# Lab_6_CTD.net
KiCad netlist of a schematic drawn in EAGLE
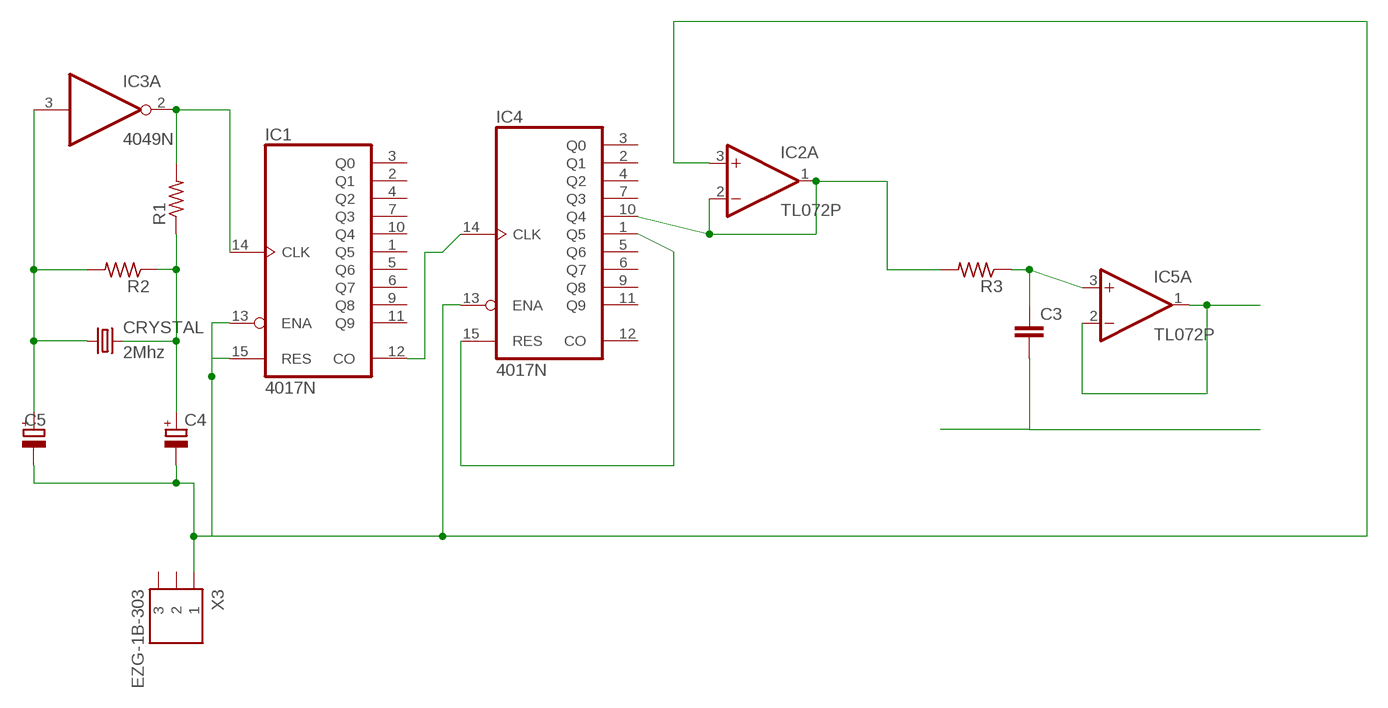
[diagram p0: schematic, sheet 1]

(export (version "E")
  (design (tool "Eeschema 10.0.6"))
  (components
    (comp (ref "C3")
      (value "C-EU050-025X075")
      (footprint "eagle-import:C050-025X075")
      (libsource (lib "eagle-import") (part "C-EU050-025X075"))
    )
    (comp (ref "C4")
      (value "CPOL-EUB45181A")
      (footprint "eagle-import:B45181A")
      (libsource (lib "eagle-import") (part "CPOL-EUB45181A"))
    )
    (comp (ref "C5")
      (value "CPOL-EUB45181A")
      (footprint "eagle-import:B45181A")
      (libsource (lib "eagle-import") (part "CPOL-EUB45181A"))
    )
    (comp (ref "CRYSTAL")
      (value "2Mhz")
      (footprint "eagle-import:HC49U-V")
      (libsource (lib "eagle-import") (part "CRYSTALHC49U-V"))
    )
    (comp (ref "IC1")
      (value "4017N")
      (footprint "eagle-import:DIL16")
      (libsource (lib "eagle-import") (part "4017N"))
    )
    (comp (ref "IC2")
      (value "TL072P")
      (footprint "eagle-import:DIL08")
      (libsource (lib "eagle-import") (part "TL072P"))
    )
    (comp (ref "IC3")
      (value "4049N")
      (footprint "eagle-import:DIL16")
      (libsource (lib "eagle-import") (part "4049N"))
    )
    (comp (ref "IC4")
      (value "4017N")
      (footprint "eagle-import:DIL16")
      (libsource (lib "eagle-import") (part "4017N"))
    )
    (comp (ref "IC5")
      (value "TL072P")
      (footprint "eagle-import:DIL08")
      (libsource (lib "eagle-import") (part "TL072P"))
    )
    (comp (ref "R1")
      (value "R-US_0411/15")
      (footprint "eagle-import:0411_15")
      (libsource (lib "eagle-import") (part "R-US_0411/15"))
    )
    (comp (ref "R2")
      (value "R-US_0411/15")
      (footprint "eagle-import:0411_15")
      (libsource (lib "eagle-import") (part "R-US_0411/15"))
    )
    (comp (ref "R3")
      (value "R-US_0411/15")
      (footprint "eagle-import:0411_15")
      (libsource (lib "eagle-import") (part "R-US_0411/15"))
    )
    (comp (ref "X3")
      (value "EZG-1B-303")
      (footprint "eagle-import:EZG-1B-1K-303")
      (libsource (lib "eagle-import") (part "EZG-?-3031B"))
    )
  )
  (nets
    (net (code "1") (name "Net-(C4-Pad+)") (class "Default")
      (node (ref "C4") (pin "+") (pinfunction "+_+") (pintype "passive"))
      (node (ref "CRYSTAL") (pin "2") (pinfunction "2_2") (pintype "passive"))
      (node (ref "R1") (pin "1") (pinfunction "1_1") (pintype "passive"))
      (node (ref "R2") (pin "1") (pinfunction "1_1") (pintype "passive"))
    )
    (net (code "2") (name "Net-(IC1A-CLK)") (class "Default")
      (node (ref "IC1") (pin "14") (pinfunction "CLK_14") (pintype "input"))
      (node (ref "IC3") (pin "2") (pinfunction "O_2") (pintype "output"))
      (node (ref "R1") (pin "2") (pinfunction "2_2") (pintype "passive"))
    )
    (net (code "3") (name "Net-(IC1A-CO)") (class "Default")
      (node (ref "IC1") (pin "12") (pinfunction "CO_12") (pintype "output"))
      (node (ref "IC4") (pin "14") (pinfunction "CLK_14") (pintype "input"))
    )
    (net (code "4") (name "Net-(IC1A-ENA)") (class "Default")
      (node (ref "C4") (pin "-") (pinfunction "-_-") (pintype "passive"))
      (node (ref "C5") (pin "-") (pinfunction "-_-") (pintype "passive"))
      (node (ref "IC1") (pin "13") (pinfunction "ENA_13") (pintype "input"))
      (node (ref "IC1") (pin "15") (pinfunction "RES_15") (pintype "input"))
      (node (ref "IC2") (pin "3") (pinfunction "+IN_3") (pintype "input"))
      (node (ref "IC4") (pin "13") (pinfunction "ENA_13") (pintype "input"))
      (node (ref "X3") (pin "1") (pinfunction "1_1") (pintype "passive"))
    )
    (net (code "5") (name "Net-(IC2A--IN)") (class "Default")
      (node (ref "IC2") (pin "1") (pinfunction "OUT_1") (pintype "output"))
      (node (ref "IC2") (pin "2") (pinfunction "-IN_2") (pintype "input"))
      (node (ref "IC4") (pin "10") (pinfunction "Q4_10") (pintype "output"))
      (node (ref "R3") (pin "2") (pinfunction "2_2") (pintype "passive"))
    )
    (net (code "6") (name "Net-(IC3A-I)") (class "Default")
      (node (ref "C5") (pin "+") (pinfunction "+_+") (pintype "passive"))
      (node (ref "CRYSTAL") (pin "1") (pinfunction "1_1") (pintype "passive"))
      (node (ref "IC3") (pin "3") (pinfunction "I_3") (pintype "input"))
      (node (ref "R2") (pin "2") (pinfunction "2_2") (pintype "passive"))
    )
    (net (code "7") (name "Net-(IC4A-Q5)") (class "Default")
      (node (ref "IC4") (pin "1") (pinfunction "Q5_1") (pintype "output"))
      (node (ref "IC4") (pin "15") (pinfunction "RES_15") (pintype "input"))
    )
    (net (code "8") (name "Net-(IC5A-+IN)") (class "Default")
      (node (ref "C3") (pin "1") (pinfunction "1_1") (pintype "passive"))
      (node (ref "IC5") (pin "3") (pinfunction "+IN_3") (pintype "input"))
      (node (ref "R3") (pin "1") (pinfunction "1_1") (pintype "passive"))
    )
    (net (code "9") (name "Net-(IC5A--IN)") (class "Default")
      (node (ref "IC5") (pin "1") (pinfunction "OUT_1") (pintype "output"))
      (node (ref "IC5") (pin "2") (pinfunction "-IN_2") (pintype "input"))
    )
    (net (code "10") (name "unconnected-(C3-Pad2)") (class "Default")
      (node (ref "C3") (pin "2") (pinfunction "2_2") (pintype "passive"))
    )
    (net (code "11") (name "unconnected-(IC1A-Q0-Pad3)") (class "Default")
      (node (ref "IC1") (pin "3") (pinfunction "Q0_3") (pintype "output"))
    )
    (net (code "12") (name "unconnected-(IC1A-Q1-Pad2)") (class "Default")
      (node (ref "IC1") (pin "2") (pinfunction "Q1_2") (pintype "output"))
    )
    (net (code "13") (name "unconnected-(IC1A-Q2-Pad4)") (class "Default")
      (node (ref "IC1") (pin "4") (pinfunction "Q2_4") (pintype "output"))
    )
    (net (code "14") (name "unconnected-(IC1A-Q3-Pad7)") (class "Default")
      (node (ref "IC1") (pin "7") (pinfunction "Q3_7") (pintype "output"))
    )
    (net (code "15") (name "unconnected-(IC1A-Q4-Pad10)") (class "Default")
      (node (ref "IC1") (pin "10") (pinfunction "Q4_10") (pintype "output"))
    )
    (net (code "16") (name "unconnected-(IC1A-Q5-Pad1)") (class "Default")
      (node (ref "IC1") (pin "1") (pinfunction "Q5_1") (pintype "output"))
    )
    (net (code "17") (name "unconnected-(IC1A-Q6-Pad5)") (class "Default")
      (node (ref "IC1") (pin "5") (pinfunction "Q6_5") (pintype "output"))
    )
    (net (code "18") (name "unconnected-(IC1A-Q7-Pad6)") (class "Default")
      (node (ref "IC1") (pin "6") (pinfunction "Q7_6") (pintype "output"))
    )
    (net (code "19") (name "unconnected-(IC1A-Q8-Pad9)") (class "Default")
      (node (ref "IC1") (pin "9") (pinfunction "Q8_9") (pintype "output"))
    )
    (net (code "20") (name "unconnected-(IC1A-Q9-Pad11)") (class "Default")
      (node (ref "IC1") (pin "11") (pinfunction "Q9_11") (pintype "output"))
    )
    (net (code "21") (name "unconnected-(IC4A-CO-Pad12)") (class "Default")
      (node (ref "IC4") (pin "12") (pinfunction "CO_12") (pintype "output"))
    )
    (net (code "22") (name "unconnected-(IC4A-Q0-Pad3)") (class "Default")
      (node (ref "IC4") (pin "3") (pinfunction "Q0_3") (pintype "output"))
    )
    (net (code "23") (name "unconnected-(IC4A-Q1-Pad2)") (class "Default")
      (node (ref "IC4") (pin "2") (pinfunction "Q1_2") (pintype "output"))
    )
    (net (code "24") (name "unconnected-(IC4A-Q2-Pad4)") (class "Default")
      (node (ref "IC4") (pin "4") (pinfunction "Q2_4") (pintype "output"))
    )
    (net (code "25") (name "unconnected-(IC4A-Q3-Pad7)") (class "Default")
      (node (ref "IC4") (pin "7") (pinfunction "Q3_7") (pintype "output"))
    )
    (net (code "26") (name "unconnected-(IC4A-Q6-Pad5)") (class "Default")
      (node (ref "IC4") (pin "5") (pinfunction "Q6_5") (pintype "output"))
    )
    (net (code "27") (name "unconnected-(IC4A-Q7-Pad6)") (class "Default")
      (node (ref "IC4") (pin "6") (pinfunction "Q7_6") (pintype "output"))
    )
    (net (code "28") (name "unconnected-(IC4A-Q8-Pad9)") (class "Default")
      (node (ref "IC4") (pin "9") (pinfunction "Q8_9") (pintype "output"))
    )
    (net (code "29") (name "unconnected-(IC4A-Q9-Pad11)") (class "Default")
      (node (ref "IC4") (pin "11") (pinfunction "Q9_11") (pintype "output"))
    )
    (net (code "30") (name "unconnected-(X3-Pad2)") (class "Default")
      (node (ref "X3") (pin "2") (pinfunction "2_2") (pintype "passive"))
    )
    (net (code "31") (name "unconnected-(X3-Pad3)") (class "Default")
      (node (ref "X3") (pin "3") (pinfunction "3_3") (pintype "passive"))
    )
  )
)
